# RF-Remute-FT.net
KiCad netlist of a schematic drawn in Altium Designer
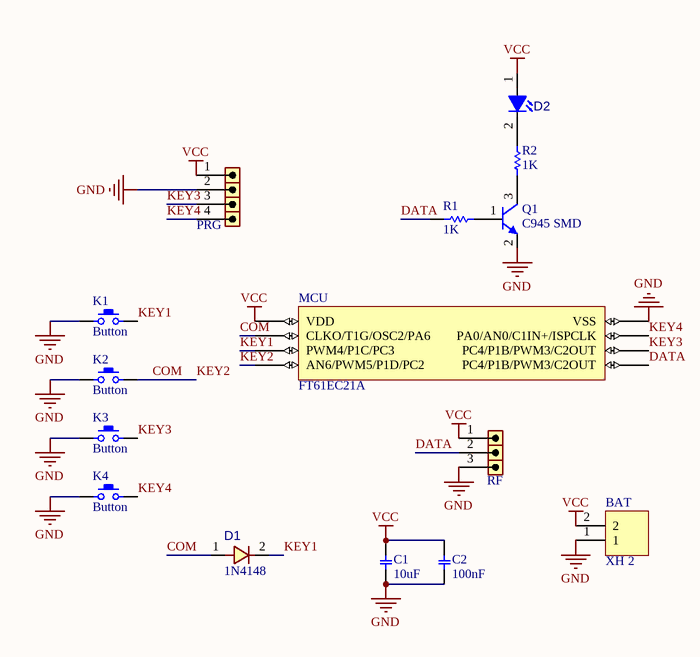
[diagram p0: RF-Remute-FT.SchDoc]

(export (version "E")
  (design (tool "Eeschema 10.0.6"))
  (components
    (comp (ref "BAT")
      (value "XH 2")
      (footprint "XH 2 PIN ( White )")
      (description "Conector XH 2 Pin")
      (libsource (lib "XH Connector") (part "Conector XH 2 Pin"))
    )
    (comp (ref "C1")
      (value "10uF")
      (footprint "C0805")
      (description "Capacitor C SMD 0805")
      (fields (field (name "Comment") "Capacitor SMD 0805"))
      (libsource (lib "Capacitor") (part "Capacitor SMD 0805"))
    )
    (comp (ref "C2")
      (value "100nF")
      (footprint "C0805")
      (description "Capacitor C SMD 0805")
      (fields (field (name "Comment") "Capacitor SMD 0805"))
      (libsource (lib "Capacitor") (part "Capacitor SMD 0805"))
    )
    (comp (ref "D1")
      (value "1N4148")
      (footprint "D_SOD80")
      (description "DIODE, FAST SWTICHING, 0.3A, 0.5W")
      (fields (field (name "Comment") "1N4148 SMD"))
      (libsource (lib "Diode") (part "1N4148 SMD"))
    )
    (comp (ref "D2")
      (value "LED SMD 0805")
      (footprint "LED SMD 0805 (Green)")
      (libsource (lib "LED") (part "LED SMD 0805"))
    )
    (comp (ref "K1")
      (value "Button")
      (footprint "BUTTON")
      (fields
        (field (name "MANUFACTURER") "Panasonic")
        (field (name "MANUFACTURER PART NUMBER") "EVQ-PE605T")
      )
      (libsource (lib "LIBM") (part "BUTTON-6.3.4-SMD"))
    )
    (comp (ref "K2")
      (value "Button")
      (footprint "BUTTON")
      (fields
        (field (name "MANUFACTURER") "Panasonic")
        (field (name "MANUFACTURER PART NUMBER") "EVQ-PE605T")
      )
      (libsource (lib "LIBM") (part "BUTTON-6.3.4-SMD"))
    )
    (comp (ref "K3")
      (value "Button")
      (footprint "BUTTON")
      (fields
        (field (name "MANUFACTURER") "Panasonic")
        (field (name "MANUFACTURER PART NUMBER") "EVQ-PE605T")
      )
      (libsource (lib "LIBM") (part "BUTTON-6.3.4-SMD"))
    )
    (comp (ref "K4")
      (value "Button")
      (footprint "BUTTON")
      (fields
        (field (name "MANUFACTURER") "Panasonic")
        (field (name "MANUFACTURER PART NUMBER") "EVQ-PE605T")
      )
      (libsource (lib "LIBM") (part "BUTTON-6.3.4-SMD"))
    )
    (comp (ref "MCU") (value "FT61EC21A") (footprint "SOP-8") (libsource (lib "HOLTEK") (part "FT61EC21A")))
    (comp (ref "PRG")
      (value "Female Header Single 4")
      (footprint "HDR_F_1X4")
      (description "Female, pitch: 2.54mm")
      (libsource (lib "Header") (part "Female Header Single 4"))
    )
    (comp (ref "Q1")
      (value "C945 SMD")
      (footprint "SOT-23")
      (fields (field (name "Comment") "C945 NPN SMD"))
      (libsource (lib "Transistor") (part "C945 NPN SMD"))
    )
    (comp (ref "R1")
      (value "1K")
      (footprint "R0805")
      (description "Resistor SMD 0805")
      (libsource (lib "Resistor") (part "Resistor SMD 0805"))
    )
    (comp (ref "R2")
      (value "1K")
      (footprint "R0805")
      (description "Resistor SMD 0805")
      (libsource (lib "Resistor") (part "Resistor SMD 0805"))
    )
    (comp (ref "RF")
      (value "Female Header Single 3")
      (footprint "HDR_F_1X3")
      (description "Female, pitch: 2.54mm")
      (libsource (lib "Header") (part "Female Header Single 3"))
    )
  )
  (nets
    (net (code "1") (name "/COM") (class "Default")
      (node (ref "D1") (pin "1") (pinfunction "1_1") (pintype "passive"))
      (node (ref "K2") (pin "2") (pinfunction "2_2") (pintype "passive"))
      (node (ref "MCU") (pin "2") (pinfunction "CLKO/T1G/OSC2/PA6_2") (pintype "bidirectional"))
      (node (ref "MCU") (pin "4") (pinfunction "AN6/PWM5/P1D/PC2_4") (pintype "bidirectional"))
    )
    (net (code "2") (name "/DATA") (class "Default")
      (node (ref "MCU") (pin "5") (pinfunction "PC4/P1B/PWM3/C2OUT_5") (pintype "bidirectional"))
      (node (ref "R1") (pin "2") (pinfunction "2_2") (pintype "passive"))
      (node (ref "RF") (pin "2") (pinfunction "2_2") (pintype "passive"))
    )
    (net (code "3") (name "/KEY1") (class "Default")
      (node (ref "D1") (pin "2") (pinfunction "2_2") (pintype "passive"))
      (node (ref "K1") (pin "2") (pinfunction "2_2") (pintype "passive"))
      (node (ref "MCU") (pin "3") (pinfunction "PWM4/P1C/PC3_3") (pintype "bidirectional"))
    )
    (net (code "4") (name "/KEY3") (class "Default")
      (node (ref "K3") (pin "2") (pinfunction "2_2") (pintype "passive"))
      (node (ref "MCU") (pin "6") (pinfunction "PC4/P1B/PWM3/C2OUT_6") (pintype "bidirectional"))
      (node (ref "PRG") (pin "3") (pinfunction "3_3") (pintype "passive"))
    )
    (net (code "5") (name "/KEY4") (class "Default")
      (node (ref "K4") (pin "2") (pinfunction "2_2") (pintype "passive"))
      (node (ref "MCU") (pin "7") (pinfunction "PA0/AN0/C1IN+/ISPCLK_7") (pintype "bidirectional"))
      (node (ref "PRG") (pin "4") (pinfunction "4_4") (pintype "passive"))
    )
    (net (code "6") (name "GND") (class "Default")
      (node (ref "BAT") (pin "1") (pinfunction "1_1") (pintype "passive"))
      (node (ref "C1") (pin "1") (pinfunction "1_1") (pintype "passive"))
      (node (ref "C2") (pin "1") (pinfunction "1_1") (pintype "passive"))
      (node (ref "K1") (pin "1") (pinfunction "1_1") (pintype "passive"))
      (node (ref "K2") (pin "1") (pinfunction "1_1") (pintype "passive"))
      (node (ref "K3") (pin "1") (pinfunction "1_1") (pintype "passive"))
      (node (ref "K4") (pin "1") (pinfunction "1_1") (pintype "passive"))
      (node (ref "MCU") (pin "8") (pinfunction "VSS_8") (pintype "bidirectional"))
      (node (ref "PRG") (pin "2") (pinfunction "2_2") (pintype "passive"))
      (node (ref "Q1") (pin "2") (pinfunction "E_2") (pintype "passive"))
      (node (ref "RF") (pin "3") (pinfunction "3_3") (pintype "passive"))
    )
    (net (code "7") (name "Net-(D2-CATHODE)") (class "Default")
      (node (ref "D2") (pin "2") (pinfunction "CATHODE_2") (pintype "passive"))
      (node (ref "R2") (pin "2") (pinfunction "2_2") (pintype "passive"))
    )
    (net (code "8") (name "Net-(Q1-B)") (class "Default")
      (node (ref "Q1") (pin "1") (pinfunction "B_1") (pintype "passive"))
      (node (ref "R1") (pin "1") (pinfunction "1_1") (pintype "passive"))
    )
    (net (code "9") (name "Net-(Q1-C)") (class "Default")
      (node (ref "Q1") (pin "3") (pinfunction "C_3") (pintype "passive"))
      (node (ref "R2") (pin "1") (pinfunction "1_1") (pintype "passive"))
    )
    (net (code "10") (name "VCC") (class "Default")
      (node (ref "BAT") (pin "2") (pinfunction "2_2") (pintype "passive"))
      (node (ref "C1") (pin "2") (pinfunction "2_2") (pintype "passive"))
      (node (ref "C2") (pin "2") (pinfunction "2_2") (pintype "passive"))
      (node (ref "D2") (pin "1") (pinfunction "ANODE_1") (pintype "passive"))
      (node (ref "MCU") (pin "1") (pinfunction "VDD_1") (pintype "bidirectional"))
      (node (ref "PRG") (pin "1") (pinfunction "1_1") (pintype "passive"))
      (node (ref "RF") (pin "1") (pinfunction "1_1") (pintype "passive"))
    )
  )
)
